# 3_-GLCD_128X64.net
KiCad netlist of a schematic drawn in Altium Designer
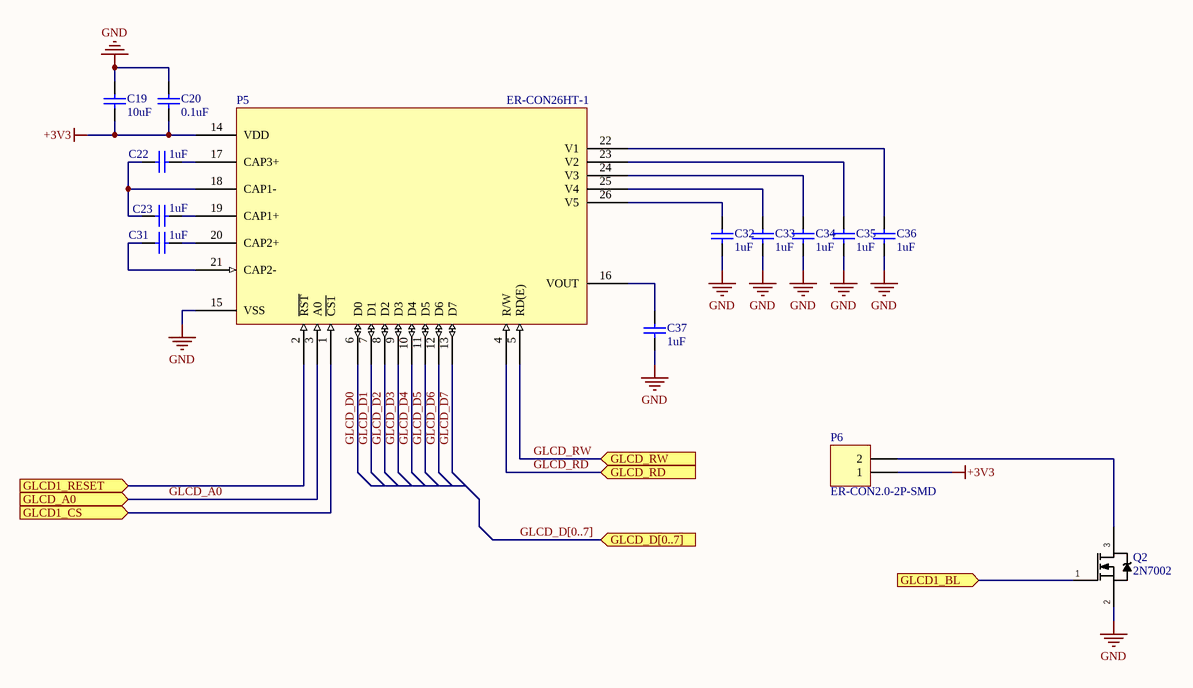
[diagram p0: [3]-GLCD_128X64.SchDoc]

(export (version "E")
  (design (tool "Eeschema 10.0.6"))
  (components
    (comp (ref "C19")
      (value "10uF")
      (footprint "CAPC1608N")
      (description "CAP CER 10UF 10V X5R 0603")
      (fields (field (name "TOLERANCE") "10%") (field (name "VOLTAGE") "10V"))
      (libsource (lib "bitsnio") (part "GRM188R61A106KE69D"))
    )
    (comp (ref "C20")
      (value "0.1uF")
      (footprint "CAPC1608N")
      (description "CAP CER 0.1UF 25V X7R 0603")
      (fields (field (name "TOLERANCE") "10%") (field (name "VOLTAGE") "25V"))
      (libsource (lib "bitsnio") (part "CC0603KRX7R8BB104"))
    )
    (comp (ref "C22")
      (value "1uF")
      (footprint "CAPC1608N")
      (description "CAP CER 1UF 35V X5R 0603")
      (libsource (lib "bitsnio") (part "CL10A105KL8NNNC"))
    )
    (comp (ref "C23")
      (value "1uF")
      (footprint "CAPC1608N")
      (description "CAP CER 1UF 35V X5R 0603")
      (libsource (lib "bitsnio") (part "CL10A105KL8NNNC"))
    )
    (comp (ref "C31")
      (value "1uF")
      (footprint "CAPC1608N")
      (description "CAP CER 1UF 35V X5R 0603")
      (libsource (lib "bitsnio") (part "CL10A105KL8NNNC"))
    )
    (comp (ref "C32")
      (value "1uF")
      (footprint "CAPC1608N")
      (description "CAP CER 1UF 35V X5R 0603")
      (libsource (lib "bitsnio") (part "CL10A105KL8NNNC"))
    )
    (comp (ref "C33")
      (value "1uF")
      (footprint "CAPC1608N")
      (description "CAP CER 1UF 35V X5R 0603")
      (libsource (lib "bitsnio") (part "CL10A105KL8NNNC"))
    )
    (comp (ref "C34")
      (value "1uF")
      (footprint "CAPC1608N")
      (description "CAP CER 1UF 35V X5R 0603")
      (libsource (lib "bitsnio") (part "CL10A105KL8NNNC"))
    )
    (comp (ref "C35")
      (value "1uF")
      (footprint "CAPC1608N")
      (description "CAP CER 1UF 35V X5R 0603")
      (libsource (lib "bitsnio") (part "CL10A105KL8NNNC"))
    )
    (comp (ref "C36")
      (value "1uF")
      (footprint "CAPC1608N")
      (description "CAP CER 1UF 35V X5R 0603")
      (libsource (lib "bitsnio") (part "CL10A105KL8NNNC"))
    )
    (comp (ref "C37")
      (value "1uF")
      (footprint "CAPC1608N")
      (description "CAP CER 1UF 35V X5R 0603")
      (libsource (lib "bitsnio") (part "CL10A105KL8NNNC"))
    )
    (comp (ref "P5")
      (value "ER-CON26HT-1")
      (footprint "ER-CON26HT-1")
      (description "CONN ZIF 26 TOP PIN SMT")
      (libsource (lib "bitsnio") (part "ER-CON26HT-1"))
    )
    (comp (ref "P6")
      (value "ER-CON2.0-2P-SMD")
      (footprint "ER-CON2.0-2P-SMD")
      (description "CONN 2 POS SMD 2MM PITCH")
      (libsource (lib "bitsnio") (part "ER-CON2.0-2P-SMD"))
    )
    (comp (ref "Q2")
      (value "2N7002")
      (footprint "SOT23-3N")
      (description "MOSFET N-CH 60V 115MA SOT-23")
      (fields (field (name "VOLTAGE") "60V"))
      (libsource (lib "bitsnio") (part "2N7002"))
    )
  )
  (nets
    (net (code "1") (name "+3V3") (class "Default")
      (node (ref "C19") (pin "1") (pinfunction "1_1") (pintype "passive"))
      (node (ref "C20") (pin "1") (pinfunction "1_1") (pintype "passive"))
      (node (ref "P5") (pin "14") (pinfunction "VDD_14") (pintype "power_in"))
      (node (ref "P6") (pin "1") (pinfunction "1_1") (pintype "passive"))
    )
    (net (code "2") (name "/GLCD1_BL") (class "Default")
      (node (ref "Q2") (pin "1") (pinfunction "G_1") (pintype "passive"))
    )
    (net (code "3") (name "/GLCD1_CS") (class "Default")
      (node (ref "P5") (pin "1") (pinfunction "~{CS1}_1") (pintype "input"))
    )
    (net (code "4") (name "/GLCD1_RESET") (class "Default")
      (node (ref "P5") (pin "2") (pinfunction "~{RST}_2") (pintype "input"))
    )
    (net (code "5") (name "/GLCD_A0") (class "Default")
      (node (ref "P5") (pin "3") (pinfunction "A0_3") (pintype "input"))
    )
    (net (code "6") (name "/GLCD_D0") (class "Default")
      (node (ref "P5") (pin "6") (pinfunction "D0_6") (pintype "bidirectional"))
    )
    (net (code "7") (name "/GLCD_D1") (class "Default")
      (node (ref "P5") (pin "7") (pinfunction "D1_7") (pintype "bidirectional"))
    )
    (net (code "8") (name "/GLCD_D2") (class "Default")
      (node (ref "P5") (pin "8") (pinfunction "D2_8") (pintype "bidirectional"))
    )
    (net (code "9") (name "/GLCD_D3") (class "Default")
      (node (ref "P5") (pin "9") (pinfunction "D3_9") (pintype "bidirectional"))
    )
    (net (code "10") (name "/GLCD_D4") (class "Default")
      (node (ref "P5") (pin "10") (pinfunction "D4_10") (pintype "bidirectional"))
    )
    (net (code "11") (name "/GLCD_D5") (class "Default")
      (node (ref "P5") (pin "11") (pinfunction "D5_11") (pintype "bidirectional"))
    )
    (net (code "12") (name "/GLCD_D6") (class "Default")
      (node (ref "P5") (pin "12") (pinfunction "D6_12") (pintype "bidirectional"))
    )
    (net (code "13") (name "/GLCD_D7") (class "Default")
      (node (ref "P5") (pin "13") (pinfunction "D7_13") (pintype "bidirectional"))
    )
    (net (code "15") (name "/GLCD_RD") (class "Default")
      (node (ref "P5") (pin "4") (pinfunction "R/W_4") (pintype "input"))
    )
    (net (code "16") (name "/GLCD_RW") (class "Default")
      (node (ref "P5") (pin "5") (pinfunction "RD(E)_5") (pintype "input"))
    )
    (net (code "17") (name "GND") (class "Default")
      (node (ref "C19") (pin "2") (pinfunction "2_2") (pintype "passive"))
      (node (ref "C20") (pin "2") (pinfunction "2_2") (pintype "passive"))
      (node (ref "C32") (pin "1") (pinfunction "1_1") (pintype "passive"))
      (node (ref "C33") (pin "1") (pinfunction "1_1") (pintype "passive"))
      (node (ref "C34") (pin "1") (pinfunction "1_1") (pintype "passive"))
      (node (ref "C35") (pin "1") (pinfunction "1_1") (pintype "passive"))
      (node (ref "C36") (pin "1") (pinfunction "1_1") (pintype "passive"))
      (node (ref "C37") (pin "1") (pinfunction "1_1") (pintype "passive"))
      (node (ref "P5") (pin "15") (pinfunction "VSS_15") (pintype "power_in"))
      (node (ref "Q2") (pin "2") (pinfunction "S_2") (pintype "passive"))
    )
    (net (code "18") (name "Net-(P5-CAP1+)") (class "Default")
      (node (ref "C23") (pin "2") (pinfunction "2_2") (pintype "passive"))
      (node (ref "P5") (pin "19") (pinfunction "CAP1+_19") (pintype "passive"))
    )
    (net (code "19") (name "Net-(P5-CAP1-)") (class "Default")
      (node (ref "C22") (pin "1") (pinfunction "1_1") (pintype "passive"))
      (node (ref "C23") (pin "1") (pinfunction "1_1") (pintype "passive"))
      (node (ref "P5") (pin "18") (pinfunction "CAP1-_18") (pintype "passive"))
    )
    (net (code "20") (name "Net-(P5-CAP2+)") (class "Default")
      (node (ref "C31") (pin "2") (pinfunction "2_2") (pintype "passive"))
      (node (ref "P5") (pin "20") (pinfunction "CAP2+_20") (pintype "power_in"))
    )
    (net (code "21") (name "Net-(P5-CAP2-)") (class "Default")
      (node (ref "C31") (pin "1") (pinfunction "1_1") (pintype "passive"))
      (node (ref "P5") (pin "21") (pinfunction "CAP2-_21") (pintype "input"))
    )
    (net (code "22") (name "Net-(P5-CAP3+)") (class "Default")
      (node (ref "C22") (pin "2") (pinfunction "2_2") (pintype "passive"))
      (node (ref "P5") (pin "17") (pinfunction "CAP3+_17") (pintype "passive"))
    )
    (net (code "23") (name "Net-(P5-V1)") (class "Default")
      (node (ref "C36") (pin "2") (pinfunction "2_2") (pintype "passive"))
      (node (ref "P5") (pin "22") (pinfunction "V1_22") (pintype "passive"))
    )
    (net (code "24") (name "Net-(P5-V2)") (class "Default")
      (node (ref "C35") (pin "2") (pinfunction "2_2") (pintype "passive"))
      (node (ref "P5") (pin "23") (pinfunction "V2_23") (pintype "passive"))
    )
    (net (code "25") (name "Net-(P5-V3)") (class "Default")
      (node (ref "C34") (pin "2") (pinfunction "2_2") (pintype "passive"))
      (node (ref "P5") (pin "24") (pinfunction "V3_24") (pintype "passive"))
    )
    (net (code "26") (name "Net-(P5-V4)") (class "Default")
      (node (ref "C33") (pin "2") (pinfunction "2_2") (pintype "passive"))
      (node (ref "P5") (pin "25") (pinfunction "V4_25") (pintype "passive"))
    )
    (net (code "27") (name "Net-(P5-V5)") (class "Default")
      (node (ref "C32") (pin "2") (pinfunction "2_2") (pintype "passive"))
      (node (ref "P5") (pin "26") (pinfunction "V5_26") (pintype "passive"))
    )
    (net (code "28") (name "Net-(P5-VOUT)") (class "Default")
      (node (ref "C37") (pin "2") (pinfunction "2_2") (pintype "passive"))
      (node (ref "P5") (pin "16") (pinfunction "VOUT_16") (pintype "passive"))
    )
    (net (code "29") (name "Net-(Q2-D)") (class "Default")
      (node (ref "P6") (pin "2") (pinfunction "2_2") (pintype "passive"))
      (node (ref "Q2") (pin "3") (pinfunction "D_3") (pintype "passive"))
    )
  )
)
